# 04_MCU.net
KiCad netlist of a schematic drawn in Altium Designer
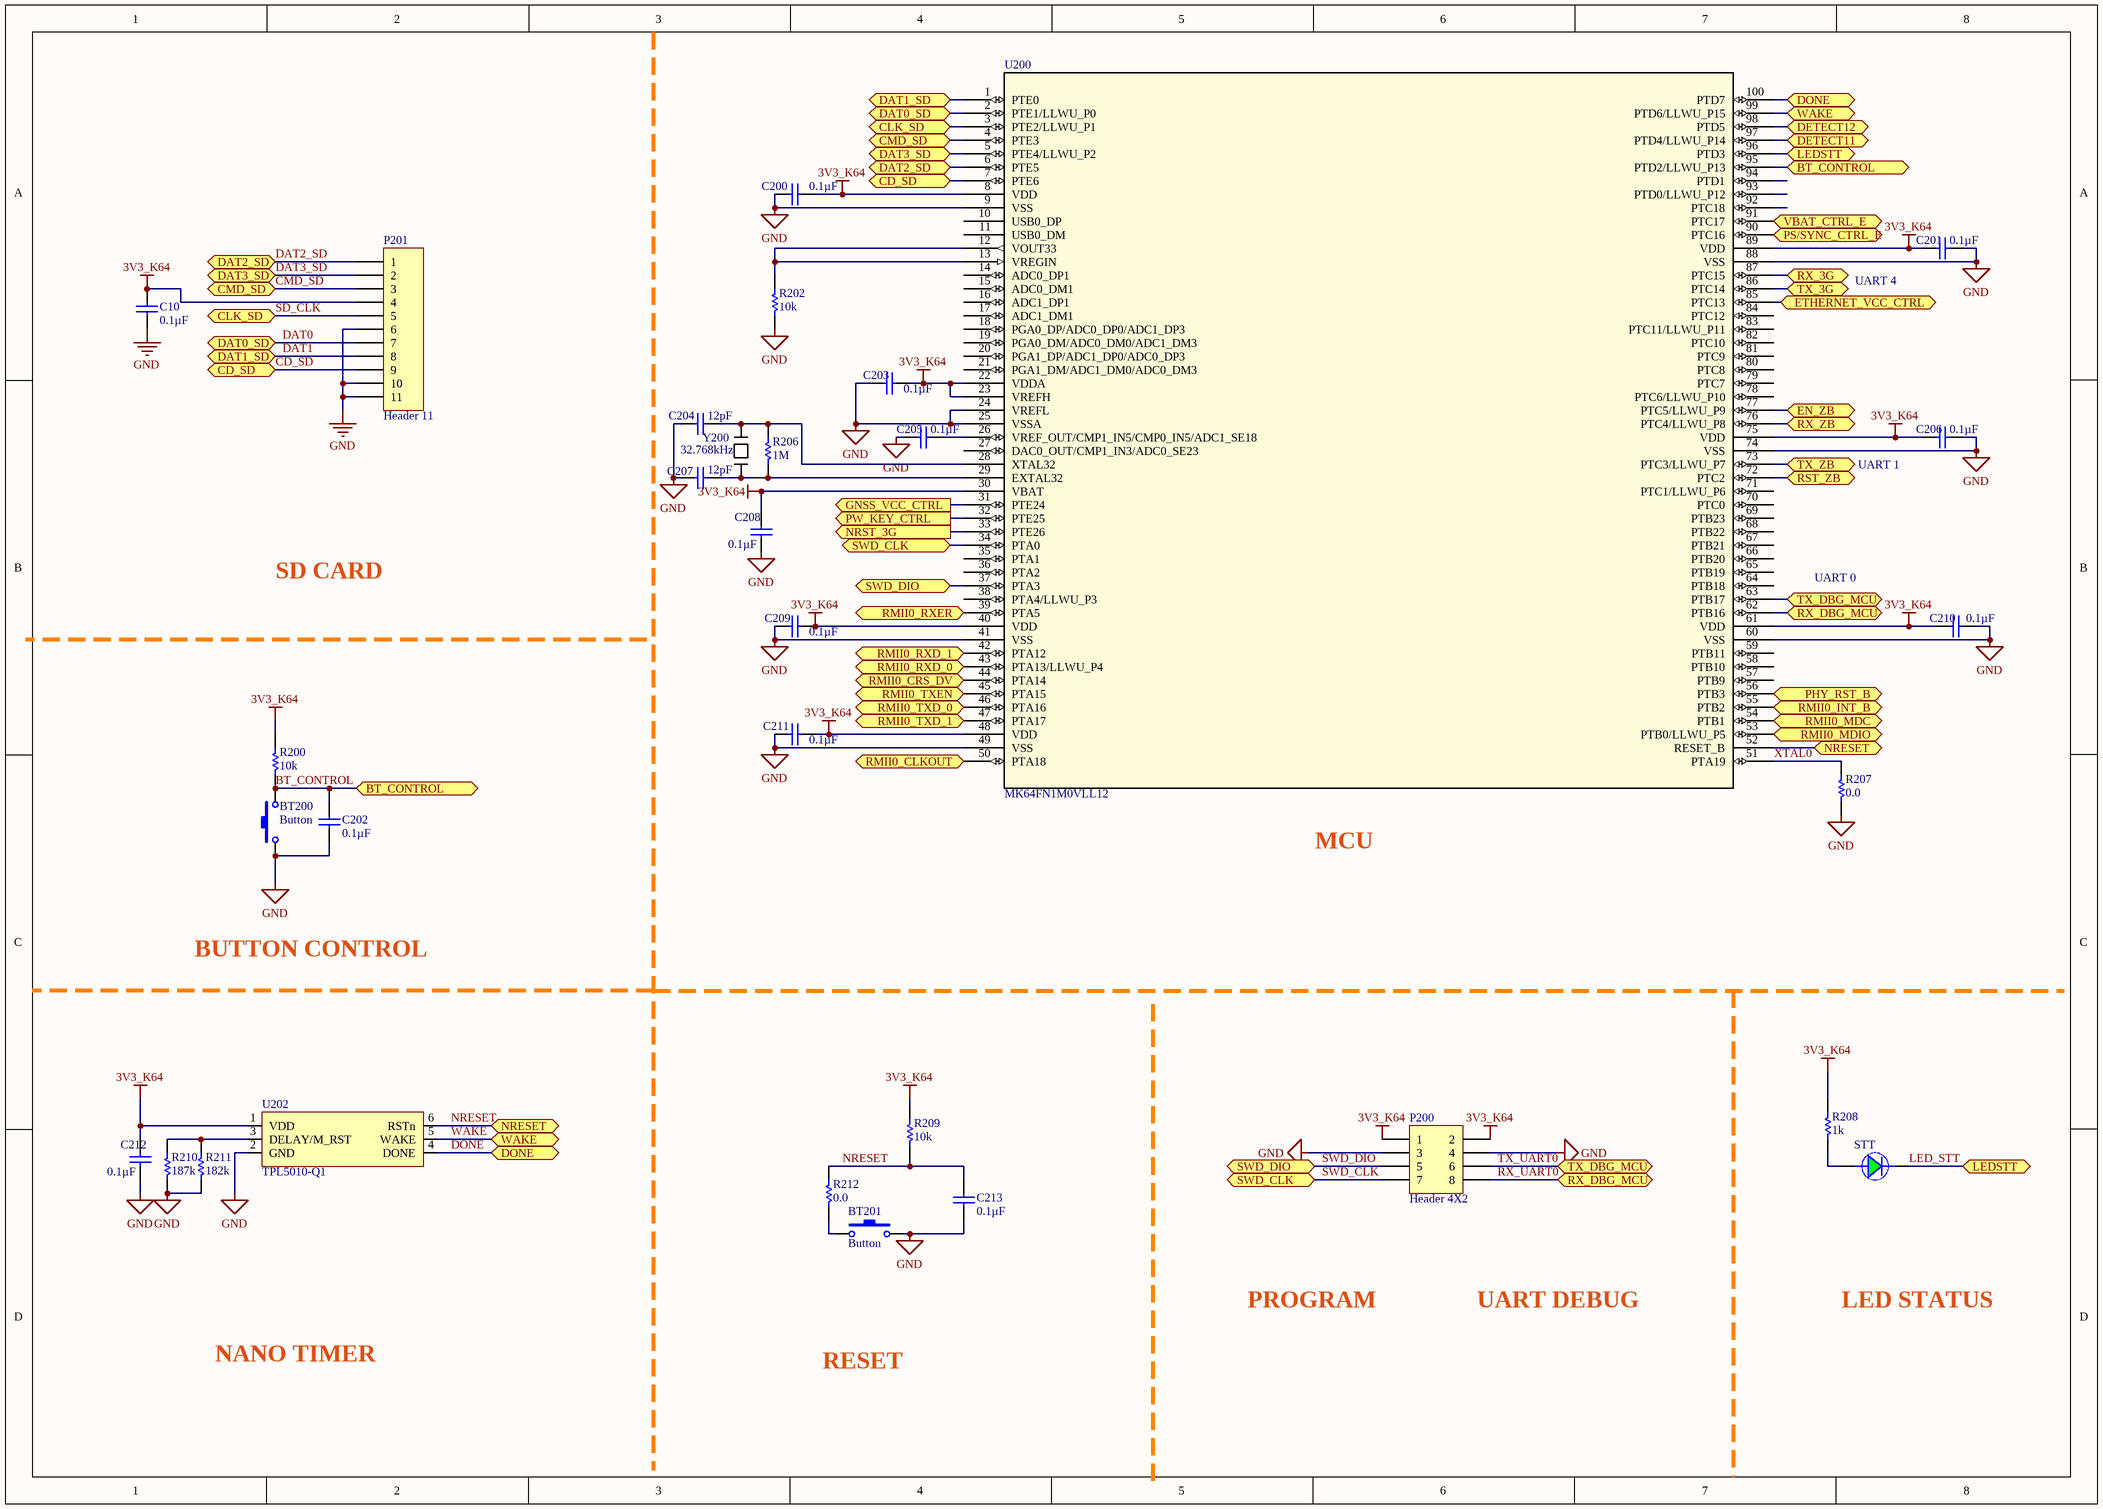
[diagram p0: [04] MCU.SchDoc]

(export (version "E")
  (design (tool "Eeschema 10.0.6"))
  (components
    (comp (ref "BT200") (value "Button") (footprint "SWSMD") (libsource (lib "BinhLib") (part "Button")))
    (comp (ref "BT201") (value "Button") (footprint "SWSMD") (libsource (lib "BinhLib") (part "Button")))
    (comp (ref "C10")
      (value "0.1µF")
      (footprint "0402C")
      (description "CAP CER 0.1UF 10V X7R 0402")
      (fields
        (field (name "MANUFACTURER") "Taiyo Yuden")
        (field (name "MANUFACTURER PART NUMBER") "LMK105B7104KVHF")
      )
      (libsource (lib "BinhLib") (part "CAP0.1u0402"))
    )
    (comp (ref "C200")
      (value "0.1µF")
      (footprint "0402C")
      (description "CAP CER 0.1UF 10V X7R 0402")
      (fields
        (field (name "MANUFACTURER") "Taiyo Yuden")
        (field (name "MANUFACTURER PART NUMBER") "LMK105B7104KVHF")
      )
      (libsource (lib "BinhLib") (part "CAP0.1u0402"))
    )
    (comp (ref "C201")
      (value "0.1µF")
      (footprint "0402C")
      (description "CAP CER 0.1UF 10V X7R 0402")
      (fields
        (field (name "MANUFACTURER") "Taiyo Yuden")
        (field (name "MANUFACTURER PART NUMBER") "LMK105B7104KVHF")
      )
      (libsource (lib "BinhLib") (part "CAP0.1u0402"))
    )
    (comp (ref "C202")
      (value "0.1µF")
      (footprint "0402C")
      (description "CAP CER 0.1UF 10V X7R 0402")
      (fields
        (field (name "MANUFACTURER") "Taiyo Yuden")
        (field (name "MANUFACTURER PART NUMBER") "LMK105B7104KVHF")
      )
      (libsource (lib "BinhLib") (part "CAP0.1u0402"))
    )
    (comp (ref "C203")
      (value "0.1µF")
      (footprint "0402C")
      (description "CAP CER 0.1UF 10V X7R 0402")
      (fields
        (field (name "MANUFACTURER") "Taiyo Yuden")
        (field (name "MANUFACTURER PART NUMBER") "LMK105B7104KVHF")
      )
      (libsource (lib "BinhLib") (part "CAP0.1u0402"))
    )
    (comp (ref "C204")
      (value "12pF")
      (footprint "0402C")
      (description "CAP CER 12PF 50V NP0 0402")
      (fields
        (field (name "MANUFACTURER") "Taiyo Yuden")
        (field (name "MANUFACTURER PART NUMBER") "UMK105CG120JV-F")
      )
      (libsource (lib "BinhLib") (part "CAP12p0402"))
    )
    (comp (ref "C205")
      (value "0.1µF")
      (footprint "0402C")
      (description "CAP CER 0.1UF 10V X7R 0402")
      (fields
        (field (name "MANUFACTURER") "Taiyo Yuden")
        (field (name "MANUFACTURER PART NUMBER") "LMK105B7104KVHF")
      )
      (libsource (lib "BinhLib") (part "CAP0.1u0402"))
    )
    (comp (ref "C206")
      (value "0.1µF")
      (footprint "0402C")
      (description "CAP CER 0.1UF 10V X7R 0402")
      (fields
        (field (name "MANUFACTURER") "Taiyo Yuden")
        (field (name "MANUFACTURER PART NUMBER") "LMK105B7104KVHF")
      )
      (libsource (lib "BinhLib") (part "CAP0.1u0402"))
    )
    (comp (ref "C207")
      (value "12pF")
      (footprint "0402C")
      (description "CAP CER 12PF 50V NP0 0402")
      (fields
        (field (name "MANUFACTURER") "Taiyo Yuden")
        (field (name "MANUFACTURER PART NUMBER") "UMK105CG120JV-F")
      )
      (libsource (lib "BinhLib") (part "CAP12p0402"))
    )
    (comp (ref "C208")
      (value "0.1µF")
      (footprint "0402C")
      (description "CAP CER 0.1UF 10V X7R 0402")
      (fields
        (field (name "MANUFACTURER") "Taiyo Yuden")
        (field (name "MANUFACTURER PART NUMBER") "LMK105B7104KVHF")
      )
      (libsource (lib "BinhLib") (part "CAP0.1u0402"))
    )
    (comp (ref "C209")
      (value "0.1µF")
      (footprint "0402C")
      (description "CAP CER 0.1UF 10V X7R 0402")
      (fields
        (field (name "MANUFACTURER") "Taiyo Yuden")
        (field (name "MANUFACTURER PART NUMBER") "LMK105B7104KVHF")
      )
      (libsource (lib "BinhLib") (part "CAP0.1u0402"))
    )
    (comp (ref "C210")
      (value "0.1µF")
      (footprint "0402C")
      (description "CAP CER 0.1UF 10V X7R 0402")
      (fields
        (field (name "MANUFACTURER") "Taiyo Yuden")
        (field (name "MANUFACTURER PART NUMBER") "LMK105B7104KVHF")
      )
      (libsource (lib "BinhLib") (part "CAP0.1u0402"))
    )
    (comp (ref "C211")
      (value "0.1µF")
      (footprint "0402C")
      (description "CAP CER 0.1UF 10V X7R 0402")
      (fields
        (field (name "MANUFACTURER") "Taiyo Yuden")
        (field (name "MANUFACTURER PART NUMBER") "LMK105B7104KVHF")
      )
      (libsource (lib "BinhLib") (part "CAP0.1u0402"))
    )
    (comp (ref "C212")
      (value "0.1µF")
      (footprint "0402C")
      (description "CAP CER 0.1UF 10V X7R 0402")
      (fields
        (field (name "MANUFACTURER") "Taiyo Yuden")
        (field (name "MANUFACTURER PART NUMBER") "LMK105B7104KVHF")
      )
      (libsource (lib "BinhLib") (part "CAP0.1u0402"))
    )
    (comp (ref "C213")
      (value "0.1µF")
      (footprint "0402C")
      (description "CAP CER 0.1UF 10V X7R 0402")
      (fields
        (field (name "MANUFACTURER") "Taiyo Yuden")
        (field (name "MANUFACTURER PART NUMBER") "LMK105B7104KVHF")
      )
      (libsource (lib "BinhLib") (part "CAP0.1u0402"))
    )
    (comp (ref "P200")
      (value "Header 4X2")
      (footprint "HDR2X4")
      (description "Header, 4-Pin, Dual row")
      (fields (field (name "PUBLISHER") "Altium Limited"))
      (libsource (lib "BinhLib") (part "Header 4X2"))
    )
    (comp (ref "P201")
      (value "Header 11")
      (footprint "TF_V3")
      (description "Header, 11-Pin")
      (fields (field (name "PUBLISHER") "Altium Limited"))
      (libsource (lib "BinhLib") (part "Header 11"))
    )
    (comp (ref "R200")
      (value "10k")
      (footprint "0603R")
      (description "RES SMD 10K OHM 1% 1/10W 0603")
      (fields
        (field (name "MANUFACTURER") "Panasonic Electronic Components")
        (field (name "MANUFACTURER PART NUMBER") "ERJ-3EKF1002V")
      )
      (libsource (lib "BinhLib") (part "RES10k0603"))
    )
    (comp (ref "R202")
      (value "10k")
      (footprint "0603R")
      (description "RES SMD 10K OHM 1% 1/10W 0603")
      (fields
        (field (name "MANUFACTURER") "Panasonic Electronic Components")
        (field (name "MANUFACTURER PART NUMBER") "ERJ-3EKF1002V")
      )
      (libsource (lib "BinhLib") (part "RES10k0603"))
    )
    (comp (ref "R206")
      (value "1M")
      (footprint "0603R")
      (description "RES SMD 1M OHM 1% 1/10W 0603")
      (fields
        (field (name "MANUFACTURER") "Panasonic Electronic Components")
        (field (name "MANUFACTURER PART NUMBER") "ERJ-3EKF1004V")
      )
      (libsource (lib "BinhLib") (part "RES1M0603"))
    )
    (comp (ref "R207")
      (value "0.0")
      (footprint "0603R")
      (description "RES SMD 0.0OHM JUMPER 1/10W 0603")
      (fields
        (field (name "MANUFACTURER") "Panasonic Electronic Components")
        (field (name "MANUFACTURER PART NUMBER") "ERJ-3GEY0R00V")
      )
      (libsource (lib "BinhLib") (part "RES00603"))
    )
    (comp (ref "R208")
      (value "1k")
      (footprint "0603R")
      (description "RES SMD 1K OHM 1% 1/10W 0603")
      (fields
        (field (name "MANUFACTURER") "Panasonic Electronic Components")
        (field (name "MANUFACTURER PART NUMBER") "ERJ-3EKF1001V")
      )
      (libsource (lib "BinhLib") (part "RES1k0603"))
    )
    (comp (ref "R209")
      (value "10k")
      (footprint "0603R")
      (description "RES SMD 10K OHM 1% 1/10W 0603")
      (fields
        (field (name "MANUFACTURER") "Panasonic Electronic Components")
        (field (name "MANUFACTURER PART NUMBER") "ERJ-3EKF1002V")
      )
      (libsource (lib "BinhLib") (part "RES10k0603"))
    )
    (comp (ref "R210")
      (value "187k")
      (footprint "0603R")
      (description "RES SMD 187K OHM 1% 1/10W 0603")
      (fields
        (field (name "MANUFACTURER") "Panasonic Electronic Components")
        (field (name "MANUFACTURER PART NUMBER") "ERJ-3EKF1873V")
      )
      (libsource (lib "BinhLib") (part "Resistor"))
    )
    (comp (ref "R211")
      (value "182k")
      (footprint "0603R")
      (description "RES SMD 182K OHM 1% 1/10W 0603")
      (fields
        (field (name "MANUFACTURER") "Panasonic Electronic Components")
        (field (name "MANUFACTURER PART NUMBER") "ERJ-3EKF1823V")
      )
      (libsource (lib "BinhLib") (part "Resistor"))
    )
    (comp (ref "R212")
      (value "0.0")
      (footprint "0603R")
      (description "RES SMD 0.0OHM JUMPER 1/10W 0603")
      (fields
        (field (name "MANUFACTURER") "Panasonic Electronic Components")
        (field (name "MANUFACTURER PART NUMBER") "ERJ-3GEY0R00V")
      )
      (libsource (lib "BinhLib") (part "RES00603"))
    )
    (comp (ref "STT")
      (value "~")
      (footprint "0603LED-GREEN")
      (description "LED GREEN CLEAR 0603 SMD")
      (fields
        (field (name "MANUFACTURER") "Everlight Electronics Co Ltd")
        (field (name "MANUFACTURER PART NUMBER") "QTLP601C4TR")
      )
      (libsource (lib "BinhLib") (part "LedGreen0603"))
    )
    (comp (ref "U200")
      (value "MK64FN1M0VLL12")
      (footprint "LQFP-100_14X14X1")
      (description "IC MCU 32BIT 1MB FLASH 100LQFP")
      (fields (field (name "MANUFACTURER") "NXP USA Inc."))
      (libsource (lib "BinhLib") (part "MK64FN1M0VLL12"))
    )
    (comp (ref "U202")
      (value "TPL5010-Q1")
      (footprint "SOT23-6")
      (description "IC TIMER W/WATCHDOG 6SOT")
      (fields
        (field (name "MANUFACTURER") "Texas Instruments")
        (field (name "MANUFACTURER PART NUMBER") "TPL5010QDDCRQ1")
      )
      (libsource (lib "BinhLib") (part "TPL5010"))
    )
    (comp (ref "Y200")
      (value "32.768kHz")
      (footprint "ABS07-crystal")
      (description "CRYSTAL 32.7680KHZ 12.5PF SMD")
      (fields
        (field (name "MANUFACTURER") "Abracon LLC")
        (field (name "MANUFACTURER PART NUMBER") "ABS07-32.768KHZ-T")
      )
      (libsource (lib "BinhLib") (part "CRYSTAL32.768"))
    )
  )
  (nets
    (net (code "1") (name "/BT_CONTROL") (class "Default")
      (node (ref "BT200") (pin "2") (pinfunction "2_2") (pintype "passive"))
      (node (ref "C202") (pin "2") (pintype "passive"))
      (node (ref "R200") (pin "2") (pinfunction "2_2") (pintype "passive"))
      (node (ref "U200") (pin "95") (pinfunction "PTD2/LLWU_P13_95") (pintype "bidirectional"))
    )
    (net (code "2") (name "/CD_SD") (class "Default")
      (node (ref "P201") (pin "9") (pinfunction "9_9") (pintype "passive"))
      (node (ref "U200") (pin "7") (pinfunction "PTE6_7") (pintype "bidirectional"))
    )
    (net (code "3") (name "/CMD_SD") (class "Default")
      (node (ref "P201") (pin "3") (pinfunction "3_3") (pintype "passive"))
      (node (ref "U200") (pin "4") (pinfunction "PTE3_4") (pintype "bidirectional"))
    )
    (net (code "4") (name "/DAT0") (class "Default")
      (node (ref "P201") (pin "7") (pinfunction "7_7") (pintype "passive"))
      (node (ref "U200") (pin "2") (pinfunction "PTE1/LLWU_P0_2") (pintype "bidirectional"))
    )
    (net (code "5") (name "/DAT1") (class "Default")
      (node (ref "P201") (pin "8") (pinfunction "8_8") (pintype "passive"))
      (node (ref "U200") (pin "1") (pinfunction "PTE0_1") (pintype "bidirectional"))
    )
    (net (code "6") (name "/DAT2_SD") (class "Default")
      (node (ref "P201") (pin "1") (pinfunction "1_1") (pintype "passive"))
      (node (ref "U200") (pin "6") (pinfunction "PTE5_6") (pintype "bidirectional"))
    )
    (net (code "7") (name "/DAT3_SD") (class "Default")
      (node (ref "P201") (pin "2") (pinfunction "2_2") (pintype "passive"))
      (node (ref "U200") (pin "5") (pinfunction "PTE4/LLWU_P2_5") (pintype "bidirectional"))
    )
    (net (code "8") (name "/DETECT11") (class "Default")
      (node (ref "U200") (pin "97") (pinfunction "PTD4/LLWU_P14_97") (pintype "bidirectional"))
    )
    (net (code "9") (name "/DETECT12") (class "Default")
      (node (ref "U200") (pin "98") (pinfunction "PTD5_98") (pintype "bidirectional"))
    )
    (net (code "10") (name "/DONE") (class "Default")
      (node (ref "U200") (pin "100") (pinfunction "PTD7_100") (pintype "bidirectional"))
      (node (ref "U202") (pin "4") (pinfunction "DONE_4") (pintype "passive"))
    )
    (net (code "11") (name "/EN_ZB") (class "Default")
      (node (ref "U200") (pin "77") (pinfunction "PTC5/LLWU_P9_77") (pintype "bidirectional"))
    )
    (net (code "12") (name "/ETHERNET_VCC_CTRL") (class "Default")
      (node (ref "U200") (pin "85") (pinfunction "PTC13_85") (pintype "bidirectional"))
    )
    (net (code "13") (name "/GNSS_VCC_CTRL") (class "Default")
      (node (ref "U200") (pin "31") (pinfunction "PTE24_31") (pintype "bidirectional"))
    )
    (net (code "14") (name "/LED_STT") (class "Default")
      (node (ref "STT") (pin "2") (pinfunction "Katot_2") (pintype "passive"))
      (node (ref "U200") (pin "96") (pinfunction "PTD3_96") (pintype "bidirectional"))
    )
    (net (code "15") (name "/NRESET") (class "Default")
      (node (ref "C213") (pin "2") (pintype "passive"))
      (node (ref "R209") (pin "2") (pinfunction "2_2") (pintype "passive"))
      (node (ref "R212") (pin "2") (pinfunction "2_2") (pintype "passive"))
      (node (ref "U200") (pin "52") (pinfunction "RESET_B_52") (pintype "passive"))
      (node (ref "U202") (pin "6") (pinfunction "RSTn_6") (pintype "passive"))
    )
    (net (code "16") (name "/NRST_3G") (class "Default")
      (node (ref "U200") (pin "33") (pinfunction "PTE26_33") (pintype "bidirectional"))
    )
    (net (code "17") (name "/PHY_RST_B") (class "Default")
      (node (ref "U200") (pin "56") (pinfunction "PTB3_56") (pintype "bidirectional"))
    )
    (net (code "18") (name "/PS{slash}SYNC_CTRL_E") (class "Default")
      (node (ref "U200") (pin "90") (pinfunction "PTC16_90") (pintype "bidirectional"))
    )
    (net (code "19") (name "/PW_KEY_CTRL") (class "Default")
      (node (ref "U200") (pin "32") (pinfunction "PTE25_32") (pintype "bidirectional"))
    )
    (net (code "20") (name "/RMII0_CLKOUT") (class "Default")
      (node (ref "U200") (pin "50") (pinfunction "PTA18_50") (pintype "bidirectional"))
    )
    (net (code "21") (name "/RMII0_CRS_DV") (class "Default")
      (node (ref "U200") (pin "44") (pinfunction "PTA14_44") (pintype "bidirectional"))
    )
    (net (code "22") (name "/RMII0_INT_B") (class "Default")
      (node (ref "U200") (pin "55") (pinfunction "PTB2_55") (pintype "bidirectional"))
    )
    (net (code "23") (name "/RMII0_MDC") (class "Default")
      (node (ref "U200") (pin "54") (pinfunction "PTB1_54") (pintype "bidirectional"))
    )
    (net (code "24") (name "/RMII0_MDIO") (class "Default")
      (node (ref "U200") (pin "53") (pinfunction "PTB0/LLWU_P5_53") (pintype "bidirectional"))
    )
    (net (code "25") (name "/RMII0_RXD_0") (class "Default")
      (node (ref "U200") (pin "43") (pinfunction "PTA13/LLWU_P4_43") (pintype "bidirectional"))
    )
    (net (code "26") (name "/RMII0_RXD_1") (class "Default")
      (node (ref "U200") (pin "42") (pinfunction "PTA12_42") (pintype "bidirectional"))
    )
    (net (code "27") (name "/RMII0_RXER") (class "Default")
      (node (ref "U200") (pin "39") (pinfunction "PTA5_39") (pintype "bidirectional"))
    )
    (net (code "28") (name "/RMII0_TXD_0") (class "Default")
      (node (ref "U200") (pin "46") (pinfunction "PTA16_46") (pintype "bidirectional"))
    )
    (net (code "29") (name "/RMII0_TXD_1") (class "Default")
      (node (ref "U200") (pin "47") (pinfunction "PTA17_47") (pintype "bidirectional"))
    )
    (net (code "30") (name "/RMII0_TXEN") (class "Default")
      (node (ref "U200") (pin "45") (pinfunction "PTA15_45") (pintype "bidirectional"))
    )
    (net (code "31") (name "/RST_ZB") (class "Default")
      (node (ref "U200") (pin "72") (pinfunction "PTC2_72") (pintype "bidirectional"))
    )
    (net (code "32") (name "/RX_3G") (class "Default")
      (node (ref "U200") (pin "87") (pinfunction "PTC15_87") (pintype "bidirectional"))
    )
    (net (code "33") (name "/RX_UART0") (class "Default")
      (node (ref "P200") (pin "8") (pinfunction "8_8") (pintype "passive"))
      (node (ref "U200") (pin "62") (pinfunction "PTB16_62") (pintype "bidirectional"))
    )
    (net (code "34") (name "/RX_ZB") (class "Default")
      (node (ref "U200") (pin "76") (pinfunction "PTC4/LLWU_P8_76") (pintype "bidirectional"))
    )
    (net (code "35") (name "/SD_CLK") (class "Default")
      (node (ref "P201") (pin "5") (pinfunction "5_5") (pintype "passive"))
      (node (ref "U200") (pin "3") (pinfunction "PTE2/LLWU_P1_3") (pintype "bidirectional"))
    )
    (net (code "36") (name "/SWD_CLK") (class "Default")
      (node (ref "P200") (pin "7") (pinfunction "7_7") (pintype "passive"))
      (node (ref "U200") (pin "34") (pinfunction "PTA0_34") (pintype "bidirectional"))
    )
    (net (code "37") (name "/SWD_DIO") (class "Default")
      (node (ref "P200") (pin "5") (pinfunction "5_5") (pintype "passive"))
      (node (ref "U200") (pin "37") (pinfunction "PTA3_37") (pintype "bidirectional"))
    )
    (net (code "38") (name "/TX_3G") (class "Default")
      (node (ref "U200") (pin "86") (pinfunction "PTC14_86") (pintype "bidirectional"))
    )
    (net (code "39") (name "/TX_UART0") (class "Default")
      (node (ref "P200") (pin "6") (pinfunction "6_6") (pintype "passive"))
      (node (ref "U200") (pin "63") (pinfunction "PTB17_63") (pintype "bidirectional"))
    )
    (net (code "40") (name "/TX_ZB") (class "Default")
      (node (ref "U200") (pin "73") (pinfunction "PTC3/LLWU_P7_73") (pintype "bidirectional"))
    )
    (net (code "41") (name "/VBAT_CTRL_E") (class "Default")
      (node (ref "U200") (pin "91") (pinfunction "PTC17_91") (pintype "bidirectional"))
    )
    (net (code "42") (name "/WAKE") (class "Default")
      (node (ref "U200") (pin "99") (pinfunction "PTD6/LLWU_P15_99") (pintype "bidirectional"))
      (node (ref "U202") (pin "5") (pinfunction "WAKE_5") (pintype "passive"))
    )
    (net (code "43") (name "/XTAL0") (class "Default")
      (node (ref "R207") (pin "2") (pinfunction "2_2") (pintype "passive"))
      (node (ref "U200") (pin "51") (pinfunction "PTA19_51") (pintype "bidirectional"))
    )
    (net (code "44") (name "3V3_K64") (class "Default")
      (node (ref "C10") (pin "1") (pintype "passive"))
      (node (ref "C200") (pin "1") (pintype "passive"))
      (node (ref "C201") (pin "1") (pintype "passive"))
      (node (ref "C203") (pin "1") (pintype "passive"))
      (node (ref "C206") (pin "1") (pintype "passive"))
      (node (ref "C208") (pin "1") (pintype "passive"))
      (node (ref "C209") (pin "2") (pintype "passive"))
      (node (ref "C210") (pin "1") (pintype "passive"))
      (node (ref "C211") (pin "2") (pintype "passive"))
      (node (ref "C212") (pin "2") (pintype "passive"))
      (node (ref "P200") (pin "1") (pinfunction "1_1") (pintype "passive"))
      (node (ref "P200") (pin "2") (pinfunction "2_2") (pintype "passive"))
      (node (ref "P201") (pin "4") (pinfunction "4_4") (pintype "passive"))
      (node (ref "R200") (pin "1") (pinfunction "1_1") (pintype "passive"))
      (node (ref "R208") (pin "2") (pinfunction "2_2") (pintype "passive"))
      (node (ref "R209") (pin "1") (pinfunction "1_1") (pintype "passive"))
      (node (ref "U200") (pin "22") (pinfunction "VDDA_22") (pintype "power_in"))
      (node (ref "U200") (pin "23") (pinfunction "VREFH_23") (pintype "power_in"))
      (node (ref "U200") (pin "30") (pinfunction "VBAT_30") (pintype "power_in"))
      (node (ref "U200") (pin "40") (pinfunction "VDD_40") (pintype "power_in"))
      (node (ref "U200") (pin "48") (pinfunction "VDD_48") (pintype "power_in"))
      (node (ref "U200") (pin "61") (pinfunction "VDD_61") (pintype "power_in"))
      (node (ref "U200") (pin "75") (pinfunction "VDD_75") (pintype "power_in"))
      (node (ref "U200") (pin "8") (pinfunction "VDD_8") (pintype "power_in"))
      (node (ref "U200") (pin "89") (pinfunction "VDD_89") (pintype "power_in"))
      (node (ref "U202") (pin "1") (pinfunction "VDD_1") (pintype "passive"))
    )
    (net (code "45") (name "GND") (class "Default")
      (node (ref "BT200") (pin "1") (pinfunction "1_1") (pintype "passive"))
      (node (ref "BT201") (pin "2") (pinfunction "2_2") (pintype "passive"))
      (node (ref "C10") (pin "2") (pintype "passive"))
      (node (ref "C200") (pin "2") (pintype "passive"))
      (node (ref "C201") (pin "2") (pintype "passive"))
      (node (ref "C202") (pin "1") (pintype "passive"))
      (node (ref "C203") (pin "2") (pintype "passive"))
      (node (ref "C204") (pin "1") (pintype "passive"))
      (node (ref "C205") (pin "2") (pintype "passive"))
      (node (ref "C206") (pin "2") (pintype "passive"))
      (node (ref "C207") (pin "1") (pintype "passive"))
      (node (ref "C208") (pin "2") (pintype "passive"))
      (node (ref "C209") (pin "1") (pintype "passive"))
      (node (ref "C210") (pin "2") (pintype "passive"))
      (node (ref "C211") (pin "1") (pintype "passive"))
      (node (ref "C212") (pin "1") (pintype "passive"))
      (node (ref "C213") (pin "1") (pintype "passive"))
      (node (ref "P200") (pin "3") (pinfunction "3_3") (pintype "passive"))
      (node (ref "P200") (pin "4") (pinfunction "4_4") (pintype "passive"))
      (node (ref "P201") (pin "10") (pinfunction "10_10") (pintype "passive"))
      (node (ref "P201") (pin "11") (pinfunction "11_11") (pintype "passive"))
      (node (ref "P201") (pin "6") (pinfunction "6_6") (pintype "passive"))
      (node (ref "R202") (pin "1") (pinfunction "1_1") (pintype "passive"))
      (node (ref "R207") (pin "1") (pinfunction "1_1") (pintype "passive"))
      (node (ref "R210") (pin "1") (pinfunction "1_1") (pintype "passive"))
      (node (ref "R211") (pin "1") (pinfunction "1_1") (pintype "passive"))
      (node (ref "U200") (pin "24") (pinfunction "VREFL_24") (pintype "power_in"))
      (node (ref "U200") (pin "25") (pinfunction "VSSA_25") (pintype "power_in"))
      (node (ref "U200") (pin "41") (pinfunction "VSS_41") (pintype "power_in"))
      (node (ref "U200") (pin "49") (pinfunction "VSS_49") (pintype "power_in"))
      (node (ref "U200") (pin "60") (pinfunction "VSS_60") (pintype "power_in"))
      (node (ref "U200") (pin "74") (pinfunction "VSS_74") (pintype "power_in"))
      (node (ref "U200") (pin "88") (pinfunction "VSS_88") (pintype "power_in"))
      (node (ref "U200") (pin "9") (pinfunction "VSS_9") (pintype "power_in"))
      (node (ref "U202") (pin "2") (pinfunction "GND_2") (pintype "passive"))
    )
    (net (code "46") (name "Net-(BT201-Pad1)") (class "Default")
      (node (ref "BT201") (pin "1") (pinfunction "1_1") (pintype "passive"))
      (node (ref "R212") (pin "1") (pinfunction "1_1") (pintype "passive"))
    )
    (net (code "47") (name "Net-(STT-anot)") (class "Default")
      (node (ref "R208") (pin "1") (pinfunction "1_1") (pintype "passive"))
      (node (ref "STT") (pin "1") (pinfunction "anot_1") (pintype "passive"))
    )
    (net (code "48") (name "Net-(U200-EXTAL32)") (class "Default")
      (node (ref "C207") (pin "2") (pintype "passive"))
      (node (ref "R206") (pin "1") (pinfunction "1_1") (pintype "passive"))
      (node (ref "U200") (pin "29") (pinfunction "EXTAL32_29") (pintype "passive"))
      (node (ref "Y200") (pin "2") (pintype "passive"))
    )
    (net (code "49") (name "Net-(U200-VOUT33)") (class "Default")
      (node (ref "R202") (pin "2") (pinfunction "2_2") (pintype "passive"))
      (node (ref "U200") (pin "12") (pinfunction "VOUT33_12") (pintype "output"))
      (node (ref "U200") (pin "13") (pinfunction "VREGIN_13") (pintype "input"))
    )
    (net (code "50") (name "Net-(U200-VREF_OUT{slash}CMP1_IN5{slash}CMP0_IN5{slash}ADC1_SE18)") (class "Default")
      (node (ref "C205") (pin "1") (pintype "passive"))
      (node (ref "U200") (pin "26") (pinfunction "VREF_OUT/CMP1_IN5/CMP0_IN5/ADC1_SE18_26") (pintype "bidirectional"))
    )
    (net (code "51") (name "Net-(U200-XTAL32)") (class "Default")
      (node (ref "C204") (pin "2") (pintype "passive"))
      (node (ref "R206") (pin "2") (pinfunction "2_2") (pintype "passive"))
      (node (ref "U200") (pin "28") (pinfunction "XTAL32_28") (pintype "passive"))
      (node (ref "Y200") (pin "1") (pintype "passive"))
    )
    (net (code "52") (name "Net-(U202-DELAY{slash}M_RST)") (class "Default")
      (node (ref "R210") (pin "2") (pinfunction "2_2") (pintype "passive"))
      (node (ref "R211") (pin "2") (pinfunction "2_2") (pintype "passive"))
      (node (ref "U202") (pin "3") (pinfunction "DELAY/M_RST_3") (pintype "passive"))
    )
    (net (code "53") (name "unconnected-(U200-ADC0_DM1-Pad15)") (class "Default")
      (node (ref "U200") (pin "15") (pinfunction "ADC0_DM1_15") (pintype "bidirectional"))
    )
    (net (code "54") (name "unconnected-(U200-ADC0_DP1-Pad14)") (class "Default")
      (node (ref "U200") (pin "14") (pinfunction "ADC0_DP1_14") (pintype "bidirectional"))
    )
    (net (code "55") (name "unconnected-(U200-ADC1_DM1-Pad17)") (class "Default")
      (node (ref "U200") (pin "17") (pinfunction "ADC1_DM1_17") (pintype "bidirectional"))
    )
    (net (code "56") (name "unconnected-(U200-ADC1_DP1-Pad16)") (class "Default")
      (node (ref "U200") (pin "16") (pinfunction "ADC1_DP1_16") (pintype "bidirectional"))
    )
    (net (code "57") (name "unconnected-(U200-DAC0_OUT{slash}CMP1_IN3{slash}ADC0_SE23-Pad27)") (class "Default")
      (node (ref "U200") (pin "27") (pinfunction "DAC0_OUT/CMP1_IN3/ADC0_SE23_27") (pintype "bidirectional"))
    )
    (net (code "58") (name "unconnected-(U200-PGA0_DM{slash}ADC0_DM0{slash}ADC1_DM3-Pad19)") (class "Default")
      (node (ref "U200") (pin "19") (pinfunction "PGA0_DM/ADC0_DM0/ADC1_DM3_19") (pintype "bidirectional"))
    )
    (net (code "59") (name "unconnected-(U200-PGA0_DP{slash}ADC0_DP0{slash}ADC1_DP3-Pad18)") (class "Default")
      (node (ref "U200") (pin "18") (pinfunction "PGA0_DP/ADC0_DP0/ADC1_DP3_18") (pintype "bidirectional"))
    )
    (net (code "60") (name "unconnected-(U200-PGA1_DM{slash}ADC1_DM0{slash}ADC0_DM3-Pad21)") (class "Default")
      (node (ref "U200") (pin "21") (pinfunction "PGA1_DM/ADC1_DM0/ADC0_DM3_21") (pintype "bidirectional"))
    )
    (net (code "61") (name "unconnected-(U200-PGA1_DP{slash}ADC1_DP0{slash}ADC0_DP3-Pad20)") (class "Default")
      (node (ref "U200") (pin "20") (pinfunction "PGA1_DP/ADC1_DP0/ADC0_DP3_20") (pintype "bidirectional"))
    )
    (net (code "62") (name "unconnected-(U200-PTA1-Pad35)") (class "Default")
      (node (ref "U200") (pin "35") (pinfunction "PTA1_35") (pintype "bidirectional"))
    )
    (net (code "63") (name "unconnected-(U200-PTA2-Pad36)") (class "Default")
      (node (ref "U200") (pin "36") (pinfunction "PTA2_36") (pintype "bidirectional"))
    )
    (net (code "64") (name "unconnected-(U200-PTA4{slash}LLWU_P3-Pad38)") (class "Default")
      (node (ref "U200") (pin "38") (pinfunction "PTA4/LLWU_P3_38") (pintype "bidirectional"))
    )
    (net (code "65") (name "unconnected-(U200-PTB9-Pad57)") (class "Default")
      (node (ref "U200") (pin "57") (pinfunction "PTB9_57") (pintype "bidirectional"))
    )
    (net (code "66") (name "unconnected-(U200-PTB10-Pad58)") (class "Default")
      (node (ref "U200") (pin "58") (pinfunction "PTB10_58") (pintype "bidirectional"))
    )
    (net (code "67") (name "unconnected-(U200-PTB11-Pad59)") (class "Default")
      (node (ref "U200") (pin "59") (pinfunction "PTB11_59") (pintype "bidirectional"))
    )
    (net (code "68") (name "unconnected-(U200-PTB18-Pad64)") (class "Default")
      (node (ref "U200") (pin "64") (pinfunction "PTB18_64") (pintype "bidirectional"))
    )
    (net (code "69") (name "unconnected-(U200-PTB19-Pad65)") (class "Default")
      (node (ref "U200") (pin "65") (pinfunction "PTB19_65") (pintype "bidirectional"))
    )
    (net (code "70") (name "unconnected-(U200-PTB20-Pad66)") (class "Default")
      (node (ref "U200") (pin "66") (pinfunction "PTB20_66") (pintype "bidirectional"))
    )
    (net (code "71") (name "unconnected-(U200-PTB21-Pad67)") (class "Default")
      (node (ref "U200") (pin "67") (pinfunction "PTB21_67") (pintype "bidirectional"))
    )
    (net (code "72") (name "unconnected-(U200-PTB22-Pad68)") (class "Default")
      (node (ref "U200") (pin "68") (pinfunction "PTB22_68") (pintype "bidirectional"))
    )
    (net (code "73") (name "unconnected-(U200-PTB23-Pad69)") (class "Default")
      (node (ref "U200") (pin "69") (pinfunction "PTB23_69") (pintype "bidirectional"))
    )
    (net (code "74") (name "unconnected-(U200-PTC0-Pad70)") (class "Default")
      (node (ref "U200") (pin "70") (pinfunction "PTC0_70") (pintype "bidirectional"))
    )
    (net (code "75") (name "unconnected-(U200-PTC1{slash}LLWU_P6-Pad71)") (class "Default")
      (node (ref "U200") (pin "71") (pinfunction "PTC1/LLWU_P6_71") (pintype "bidirectional"))
    )
    (net (code "76") (name "unconnected-(U200-PTC6{slash}LLWU_P10-Pad78)") (class "Default")
      (node (ref "U200") (pin "78") (pinfunction "PTC6/LLWU_P10_78") (pintype "bidirectional"))
    )
    (net (code "77") (name "unconnected-(U200-PTC7-Pad79)") (class "Default")
      (node (ref "U200") (pin "79") (pinfunction "PTC7_79") (pintype "bidirectional"))
    )
    (net (code "78") (name "unconnected-(U200-PTC8-Pad80)") (class "Default")
      (node (ref "U200") (pin "80") (pinfunction "PTC8_80") (pintype "bidirectional"))
    )
    (net (code "79") (name "unconnected-(U200-PTC9-Pad81)") (class "Default")
      (node (ref "U200") (pin "81") (pinfunction "PTC9_81") (pintype "bidirectional"))
    )
    (net (code "80") (name "unconnected-(U200-PTC10-Pad82)") (class "Default")
      (node (ref "U200") (pin "82") (pinfunction "PTC10_82") (pintype "bidirectional"))
    )
    (net (code "81") (name "unconnected-(U200-PTC11{slash}LLWU_P11-Pad83)") (class "Default")
      (node (ref "U200") (pin "83") (pinfunction "PTC11/LLWU_P11_83") (pintype "bidirectional"))
    )
    (net (code "82") (name "unconnected-(U200-PTC12-Pad84)") (class "Default")
      (node (ref "U200") (pin "84") (pinfunction "PTC12_84") (pintype "bidirectional"))
    )
    (net (code "83") (name "unconnected-(U200-PTC18-Pad92)") (class "Default")
      (node (ref "U200") (pin "92") (pinfunction "PTC18_92") (pintype "bidirectional"))
    )
    (net (code "84") (name "unconnected-(U200-PTD0{slash}LLWU_P12-Pad93)") (class "Default")
      (node (ref "U200") (pin "93") (pinfunction "PTD0/LLWU_P12_93") (pintype "bidirectional"))
    )
    (net (code "85") (name "unconnected-(U200-PTD1-Pad94)") (class "Default")
      (node (ref "U200") (pin "94") (pinfunction "PTD1_94") (pintype "bidirectional"))
    )
    (net (code "86") (name "unconnected-(U200-USB0_DM-Pad11)") (class "Default")
      (node (ref "U200") (pin "11") (pinfunction "USB0_DM_11") (pintype "passive"))
    )
    (net (code "87") (name "unconnected-(U200-USB0_DP-Pad10)") (class "Default")
      (node (ref "U200") (pin "10") (pinfunction "USB0_DP_10") (pintype "passive"))
    )
  )
)
